# esp-socket-4.net
KiCad netlist of a schematic drawn in EAGLE
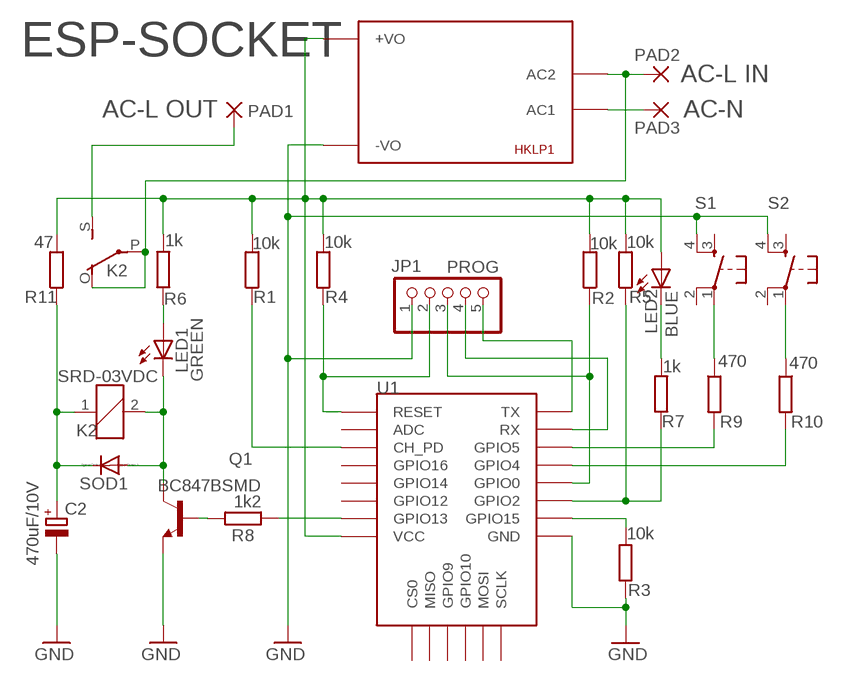
[diagram p0: schematic, sheet 1]

(export (version "E")
  (design (tool "Eeschema 10.0.6"))
  (components
    (comp (ref "C2")
      (value "470uF/10V")
      (footprint "eagle-import:E3,5-8-B")
      (libsource (lib "eagle-import") (part "CPOL-EUE3,5-8-B"))
    )
    (comp (ref "HKLP1")
      (value "HKLPM01")
      (footprint "eagle-import:HKLPM01")
      (libsource (lib "eagle-import") (part "HKLPM01"))
    )
    (comp (ref "JP1")
      (value "PROG")
      (footprint "eagle-import:1X05-2B")
      (libsource (lib "eagle-import") (part "PINHD-1X51X05-2B"))
    )
    (comp (ref "K2")
      (value "SRD-03VDC")
      (footprint "eagle-import:G5L-2B")
      (libsource (lib "eagle-import") (part "G5L-2B"))
    )
    (comp (ref "LED1")
      (value "GREEN")
      (footprint "eagle-import:LED3MM-B")
      (libsource (lib "eagle-import") (part "LEDB"))
    )
    (comp (ref "LED2")
      (value "BLUE")
      (footprint "eagle-import:LED3MM-B")
      (libsource (lib "eagle-import") (part "LEDB"))
    )
    (comp (ref "PAD1")
      (value "3,17/1,1")
      (footprint "eagle-import:3,17_1,1")
      (libsource (lib "eagle-import") (part "3,17/1,1"))
    )
    (comp (ref "PAD2")
      (value "3,17/1,1")
      (footprint "eagle-import:3,17_1,1")
      (libsource (lib "eagle-import") (part "3,17/1,1"))
    )
    (comp (ref "PAD3")
      (value "3,17/1,1")
      (footprint "eagle-import:3,17_1,1")
      (libsource (lib "eagle-import") (part "3,17/1,1"))
    )
    (comp (ref "Q1")
      (value "BC847BSMD")
      (footprint "eagle-import:SOT23")
      (libsource (lib "eagle-import") (part "BC847SMDB"))
    )
    (comp (ref "R1")
      (value "10k")
      (footprint "eagle-import:M1206")
      (libsource (lib "eagle-import") (part "R-EU_M1206"))
    )
    (comp (ref "R2")
      (value "10k")
      (footprint "eagle-import:M1206")
      (libsource (lib "eagle-import") (part "R-EU_M1206"))
    )
    (comp (ref "R3")
      (value "10k")
      (footprint "eagle-import:M1206")
      (libsource (lib "eagle-import") (part "R-EU_M1206"))
    )
    (comp (ref "R4")
      (value "10k")
      (footprint "eagle-import:M1206")
      (libsource (lib "eagle-import") (part "R-EU_M1206"))
    )
    (comp (ref "R5")
      (value "10k")
      (footprint "eagle-import:M1206")
      (libsource (lib "eagle-import") (part "R-EU_M1206"))
    )
    (comp (ref "R6")
      (value "1k")
      (footprint "eagle-import:M1206")
      (libsource (lib "eagle-import") (part "R-EU_M1206"))
    )
    (comp (ref "R7")
      (value "1k")
      (footprint "eagle-import:M1206")
      (libsource (lib "eagle-import") (part "R-EU_M1206"))
    )
    (comp (ref "R8")
      (value "1k2")
      (footprint "eagle-import:M1206")
      (libsource (lib "eagle-import") (part "R-EU_M1206"))
    )
    (comp (ref "R9")
      (value "470")
      (footprint "eagle-import:M1206")
      (libsource (lib "eagle-import") (part "R-EU_M1206"))
    )
    (comp (ref "R10")
      (value "470")
      (footprint "eagle-import:M1206")
      (libsource (lib "eagle-import") (part "R-EU_M1206"))
    )
    (comp (ref "R11")
      (value "47")
      (footprint "eagle-import:0207_10-2B")
      (libsource (lib "eagle-import") (part "R-EU_0207/10-2B"))
    )
    (comp (ref "S1")
      (value "DTS-6-B")
      (footprint "eagle-import:DTS-6-B")
      (libsource (lib "eagle-import") (part "DTS-6-B"))
    )
    (comp (ref "S2")
      (value "DTS-6-B")
      (footprint "eagle-import:DTS-6-B")
      (libsource (lib "eagle-import") (part "DTS-6-B"))
    )
    (comp (ref "SOD1")
      (value "DIODE-MELF-MLL41")
      (footprint "eagle-import:MELF-MLL41")
      (libsource (lib "eagle-import") (part "DIODE-MELF-MLL41"))
    )
    (comp (ref "U1")
      (value "ESP12ESMD")
      (footprint "eagle-import:ESP12E-SMD")
      (libsource (lib "eagle-import") (part "ESP12ESMD"))
    )
  )
  (nets
    (net (code "1") (name "GND") (class "Default")
      (node (ref "C2") (pin "-") (pinfunction "-_-") (pintype "passive"))
      (node (ref "HKLP1") (pin "P$3") (pinfunction "-VO_P$3") (pintype "output"))
      (node (ref "JP1") (pin "1") (pinfunction "1_1") (pintype "passive"))
      (node (ref "Q1") (pin "2") (pinfunction "E_2") (pintype "passive"))
      (node (ref "R3") (pin "1") (pinfunction "1_1") (pintype "passive"))
      (node (ref "S1") (pin "4") (pinfunction "4_4") (pintype "passive"))
      (node (ref "S2") (pin "4") (pinfunction "4_4") (pintype "passive"))
      (node (ref "U1") (pin "GND") (pinfunction "GND_GND") (pintype "bidirectional"))
    )
    (net (code "2") (name "Net-(C2-Pad+)") (class "Default")
      (node (ref "C2") (pin "+") (pinfunction "+_+") (pintype "passive"))
      (node (ref "K2") (pin "1") (pinfunction "1_1") (pintype "passive"))
      (node (ref "R11") (pin "1") (pinfunction "1_1") (pintype "passive"))
      (node (ref "SOD1") (pin "C") (pinfunction "C_C") (pintype "passive"))
    )
    (net (code "3") (name "Net-(HKLP1-+VO)") (class "Default")
      (node (ref "HKLP1") (pin "P$4") (pinfunction "+VO_P$4") (pintype "output"))
      (node (ref "LED2") (pin "A") (pinfunction "A_A") (pintype "passive"))
      (node (ref "R1") (pin "2") (pinfunction "2_2") (pintype "passive"))
      (node (ref "R11") (pin "2") (pinfunction "2_2") (pintype "passive"))
      (node (ref "R2") (pin "2") (pinfunction "2_2") (pintype "passive"))
      (node (ref "R4") (pin "2") (pinfunction "2_2") (pintype "passive"))
      (node (ref "R5") (pin "2") (pinfunction "2_2") (pintype "passive"))
      (node (ref "R6") (pin "2") (pinfunction "2_2") (pintype "passive"))
      (node (ref "U1") (pin "VCC") (pinfunction "VCC_VCC") (pintype "bidirectional"))
    )
    (net (code "4") (name "Net-(HKLP1-AC1)") (class "Default")
      (node (ref "HKLP1") (pin "P$1") (pinfunction "AC1_P$1") (pintype "power_in"))
      (node (ref "PAD3") (pin "1") (pinfunction "P_1") (pintype "passive"))
    )
    (net (code "5") (name "Net-(HKLP1-AC2)") (class "Default")
      (node (ref "HKLP1") (pin "P$2") (pinfunction "AC2_P$2") (pintype "power_in"))
      (node (ref "K2") (pin "O") (pinfunction "O_O") (pintype "passive"))
      (node (ref "K2") (pin "P") (pinfunction "P_P") (pintype "passive"))
      (node (ref "PAD2") (pin "1") (pinfunction "P_1") (pintype "passive"))
    )
    (net (code "6") (name "Net-(JP1-Pad2)") (class "Default")
      (node (ref "JP1") (pin "2") (pinfunction "2_2") (pintype "passive"))
      (node (ref "R4") (pin "1") (pinfunction "1_1") (pintype "passive"))
      (node (ref "U1") (pin "RESET") (pinfunction "RESET_RESET") (pintype "bidirectional"))
    )
    (net (code "7") (name "Net-(JP1-Pad3)") (class "Default")
      (node (ref "JP1") (pin "3") (pinfunction "3_3") (pintype "passive"))
      (node (ref "R2") (pin "1") (pinfunction "1_1") (pintype "passive"))
      (node (ref "U1") (pin "GPIO0") (pinfunction "GPIO0_GPIO0") (pintype "bidirectional"))
    )
    (net (code "8") (name "Net-(LED1-C)") (class "Default")
      (node (ref "K2") (pin "2") (pinfunction "2_2") (pintype "passive"))
      (node (ref "LED1") (pin "K") (pinfunction "C_K") (pintype "passive"))
      (node (ref "Q1") (pin "3") (pinfunction "C_3") (pintype "passive"))
      (node (ref "SOD1") (pin "A") (pinfunction "A_A") (pintype "passive"))
    )
    (net (code "9") (name "Net-(LED1-PadA)") (class "Default")
      (node (ref "LED1") (pin "A") (pinfunction "A_A") (pintype "passive"))
      (node (ref "R6") (pin "1") (pinfunction "1_1") (pintype "passive"))
    )
    (net (code "10") (name "Net-(LED2-C)") (class "Default")
      (node (ref "LED2") (pin "K") (pinfunction "C_K") (pintype "passive"))
      (node (ref "R7") (pin "2") (pinfunction "2_2") (pintype "passive"))
    )
    (net (code "11") (name "Net-(PAD1-P)") (class "Default")
      (node (ref "K2") (pin "S") (pinfunction "S_S") (pintype "passive"))
      (node (ref "PAD1") (pin "1") (pinfunction "P_1") (pintype "passive"))
    )
    (net (code "12") (name "Net-(Q1-B)") (class "Default")
      (node (ref "Q1") (pin "1") (pinfunction "B_1") (pintype "passive"))
      (node (ref "R8") (pin "2") (pinfunction "2_2") (pintype "passive"))
    )
    (net (code "13") (name "Net-(R1-Pad1)") (class "Default")
      (node (ref "R1") (pin "1") (pinfunction "1_1") (pintype "passive"))
      (node (ref "U1") (pin "CH_PD") (pinfunction "CH_PD_CH_PD") (pintype "bidirectional"))
    )
    (net (code "14") (name "Net-(R3-Pad2)") (class "Default")
      (node (ref "R3") (pin "2") (pinfunction "2_2") (pintype "passive"))
      (node (ref "U1") (pin "GPIO15") (pinfunction "GPIO15_GPIO15") (pintype "bidirectional"))
    )
    (net (code "15") (name "Net-(R5-Pad1)") (class "Default")
      (node (ref "R5") (pin "1") (pinfunction "1_1") (pintype "passive"))
      (node (ref "R7") (pin "1") (pinfunction "1_1") (pintype "passive"))
      (node (ref "U1") (pin "GPIO2") (pinfunction "GPIO2_GPIO2") (pintype "bidirectional"))
    )
    (net (code "16") (name "Net-(R8-Pad1)") (class "Default")
      (node (ref "R8") (pin "1") (pinfunction "1_1") (pintype "passive"))
      (node (ref "U1") (pin "GPIO13") (pinfunction "GPIO13_GPIO13") (pintype "bidirectional"))
    )
    (net (code "17") (name "Net-(R9-Pad1)") (class "Default")
      (node (ref "R9") (pin "1") (pinfunction "1_1") (pintype "passive"))
      (node (ref "S1") (pin "1") (pinfunction "1_1") (pintype "passive"))
    )
    (net (code "18") (name "Net-(R9-Pad2)") (class "Default")
      (node (ref "R9") (pin "2") (pinfunction "2_2") (pintype "passive"))
      (node (ref "U1") (pin "GPIO5") (pinfunction "GPIO5_GPIO5") (pintype "bidirectional"))
    )
    (net (code "19") (name "Net-(R10-Pad1)") (class "Default")
      (node (ref "R10") (pin "1") (pinfunction "1_1") (pintype "passive"))
      (node (ref "S2") (pin "1") (pinfunction "1_1") (pintype "passive"))
    )
    (net (code "20") (name "Net-(R10-Pad2)") (class "Default")
      (node (ref "R10") (pin "2") (pinfunction "2_2") (pintype "passive"))
      (node (ref "U1") (pin "GPIO4") (pinfunction "GPIO4_GPIO4") (pintype "bidirectional"))
    )
    (net (code "21") (name "Net-(U1-RX)") (class "Default")
      (node (ref "JP1") (pin "4") (pinfunction "4_4") (pintype "passive"))
      (node (ref "U1") (pin "RXD0") (pinfunction "RX_RXD0") (pintype "bidirectional"))
    )
    (net (code "22") (name "Net-(U1-TX)") (class "Default")
      (node (ref "JP1") (pin "5") (pinfunction "5_5") (pintype "passive"))
      (node (ref "U1") (pin "TXD0") (pinfunction "TX_TXD0") (pintype "bidirectional"))
    )
    (net (code "23") (name "unconnected-(S1-Pad2)") (class "Default")
      (node (ref "S1") (pin "2") (pinfunction "2_2") (pintype "passive"))
    )
    (net (code "24") (name "unconnected-(S1-Pad3)") (class "Default")
      (node (ref "S1") (pin "3") (pinfunction "3_3") (pintype "passive"))
    )
    (net (code "25") (name "unconnected-(S2-Pad2)") (class "Default")
      (node (ref "S2") (pin "2") (pinfunction "2_2") (pintype "passive"))
    )
    (net (code "26") (name "unconnected-(S2-Pad3)") (class "Default")
      (node (ref "S2") (pin "3") (pinfunction "3_3") (pintype "passive"))
    )
    (net (code "27") (name "unconnected-(U1-PadADC)") (class "Default")
      (node (ref "U1") (pin "ADC") (pinfunction "ADC_ADC") (pintype "bidirectional"))
    )
    (net (code "28") (name "unconnected-(U1-PadCS0)") (class "Default")
      (node (ref "U1") (pin "CS0") (pinfunction "CS0_CS0") (pintype "bidirectional"))
    )
    (net (code "29") (name "unconnected-(U1-PadGPIO9)") (class "Default")
      (node (ref "U1") (pin "GPIO9") (pinfunction "GPIO9_GPIO9") (pintype "bidirectional"))
    )
    (net (code "30") (name "unconnected-(U1-PadGPIO10)") (class "Default")
      (node (ref "U1") (pin "GPIO10") (pinfunction "GPIO10_GPIO10") (pintype "bidirectional"))
    )
    (net (code "31") (name "unconnected-(U1-PadGPIO12)") (class "Default")
      (node (ref "U1") (pin "GPIO12") (pinfunction "GPIO12_GPIO12") (pintype "bidirectional"))
    )
    (net (code "32") (name "unconnected-(U1-PadGPIO14)") (class "Default")
      (node (ref "U1") (pin "GPIO14") (pinfunction "GPIO14_GPIO14") (pintype "bidirectional"))
    )
    (net (code "33") (name "unconnected-(U1-PadGPIO16)") (class "Default")
      (node (ref "U1") (pin "GPIO16") (pinfunction "GPIO16_GPIO16") (pintype "bidirectional"))
    )
    (net (code "34") (name "unconnected-(U1-PadMISO)") (class "Default")
      (node (ref "U1") (pin "MISO") (pinfunction "MISO_MISO") (pintype "bidirectional"))
    )
    (net (code "35") (name "unconnected-(U1-PadMOSI)") (class "Default")
      (node (ref "U1") (pin "MOSI") (pinfunction "MOSI_MOSI") (pintype "bidirectional"))
    )
    (net (code "36") (name "unconnected-(U1-PadSCLK)") (class "Default")
      (node (ref "U1") (pin "SCLK") (pinfunction "SCLK_SCLK") (pintype "bidirectional"))
    )
  )
)
